# Pg4-Current_signal_condtioning.net
KiCad netlist of a schematic drawn in Altium Designer
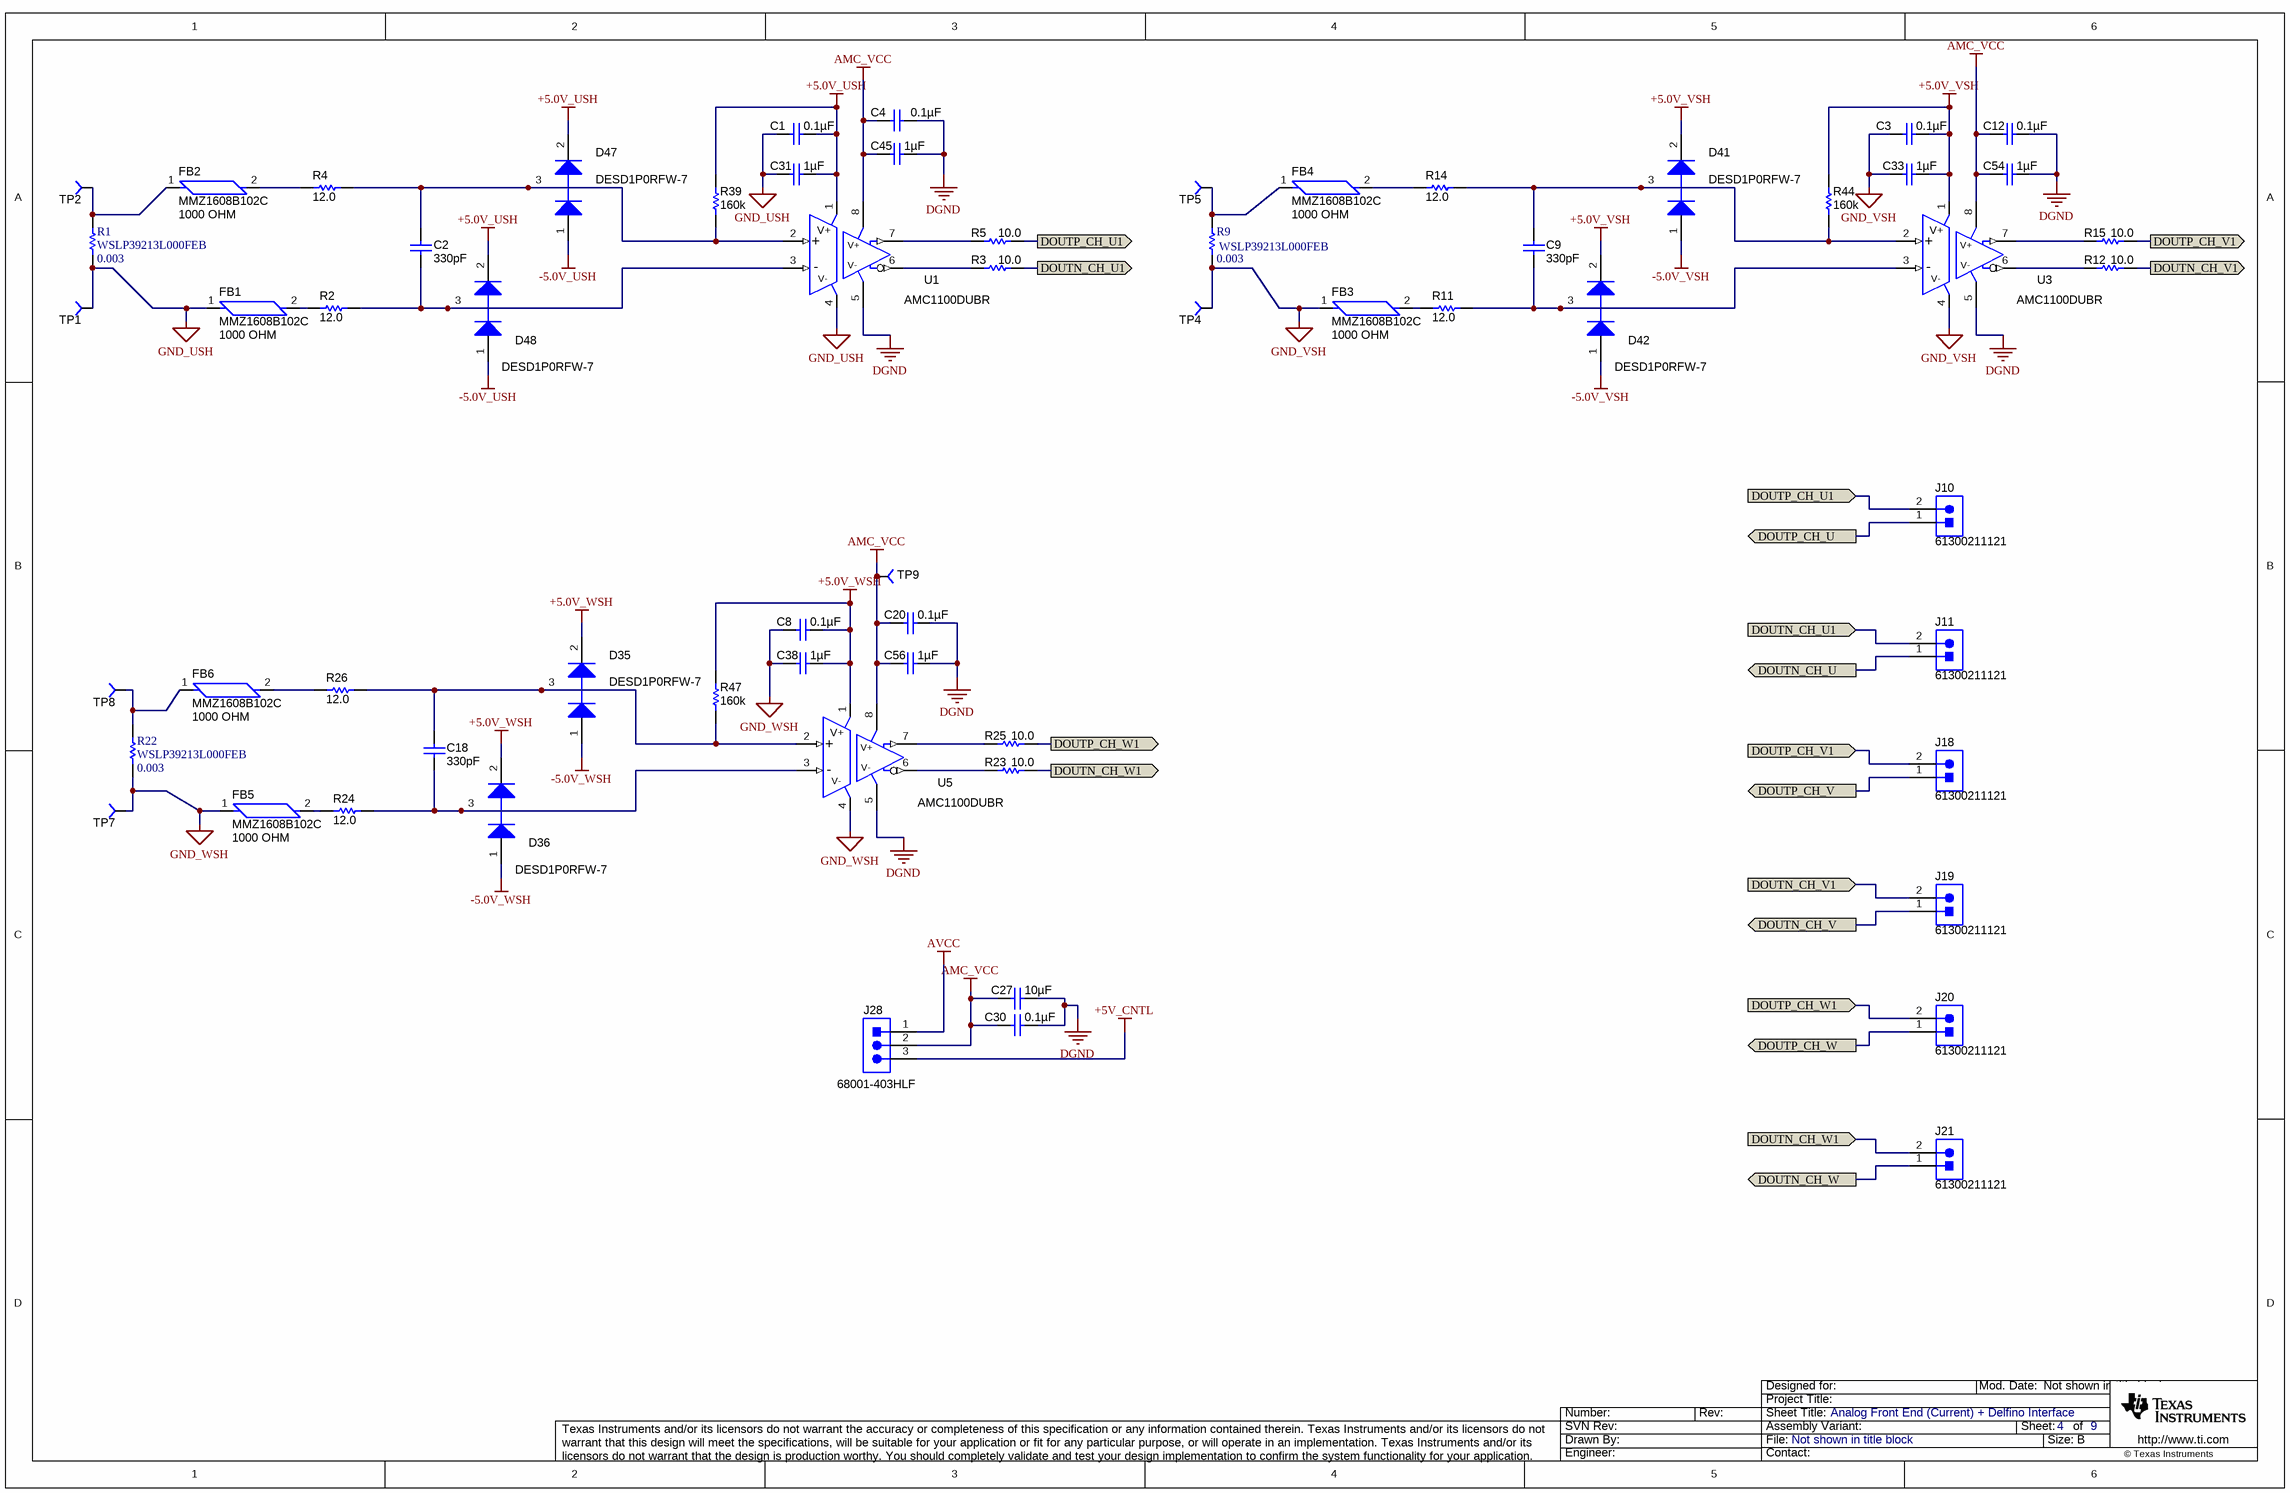
[diagram p0: Pg4-Current  signal condtioning.SchDoc]

(export (version "E")
  (design (tool "Eeschema 10.0.6"))
  (components
    (comp (ref "C1")
      (value "~")
      (footprint "0603")
      (description "CAP, CERM, 0.1uF, 25V, +/-5%, X7R, 0603")
      (fields
        (field (name "PARTNUMBER") "06033C104JAT2A")
        (field (name "VALUEDISPLAYED") "0.1µF")
        (field (name "MANUFACTURER") "AVX")
        (field (name "PUBLISHER") "Texas Instruments")
      )
      (libsource (lib "Capacitor_Ceramic") (part "06033C104JAT2A"))
    )
    (comp (ref "C2")
      (value "08055A331KAT2A")
      (footprint "0805_HV")
      (description "CAP, CERM, 330 pF, 50 V, +/- 10%, C0G/NP0, 0805")
      (fields
        (field (name "VALUEDISPLAYED") "330pF")
        (field (name "MANUFACTURER") "AVX")
        (field (name "PUBLISHER") "Texas Instruments")
      )
      (libsource (lib "Capacitor_Ceramic") (part "08055A331KAT2A"))
    )
    (comp (ref "C3")
      (value "~")
      (footprint "0603")
      (description "CAP, CERM, 0.1uF, 25V, +/-5%, X7R, 0603")
      (fields
        (field (name "PARTNUMBER") "06033C104JAT2A")
        (field (name "VALUEDISPLAYED") "0.1µF")
        (field (name "MANUFACTURER") "AVX")
        (field (name "PUBLISHER") "Texas Instruments")
      )
      (libsource (lib "Capacitor_Ceramic") (part "06033C104JAT2A"))
    )
    (comp (ref "C4")
      (value "~")
      (footprint "0603")
      (description "CAP, CERM, 0.1uF, 25V, +/-5%, X7R, 0603")
      (fields
        (field (name "PARTNUMBER") "06033C104JAT2A")
        (field (name "VALUEDISPLAYED") "0.1µF")
        (field (name "MANUFACTURER") "AVX")
        (field (name "PUBLISHER") "Texas Instruments")
      )
      (libsource (lib "Capacitor_Ceramic") (part "06033C104JAT2A"))
    )
    (comp (ref "C8")
      (value "~")
      (footprint "0603")
      (description "CAP, CERM, 0.1uF, 25V, +/-5%, X7R, 0603")
      (fields
        (field (name "PARTNUMBER") "06033C104JAT2A")
        (field (name "VALUEDISPLAYED") "0.1µF")
        (field (name "MANUFACTURER") "AVX")
        (field (name "PUBLISHER") "Texas Instruments")
      )
      (libsource (lib "Capacitor_Ceramic") (part "06033C104JAT2A"))
    )
    (comp (ref "C9")
      (value "08055A331KAT2A")
      (footprint "0805_HV")
      (description "CAP, CERM, 330 pF, 50 V, +/- 10%, C0G/NP0, 0805")
      (fields
        (field (name "VALUEDISPLAYED") "330pF")
        (field (name "MANUFACTURER") "AVX")
        (field (name "PUBLISHER") "Texas Instruments")
      )
      (libsource (lib "Capacitor_Ceramic") (part "08055A331KAT2A"))
    )
    (comp (ref "C12")
      (value "~")
      (footprint "0603")
      (description "CAP, CERM, 0.1uF, 25V, +/-5%, X7R, 0603")
      (fields
        (field (name "PARTNUMBER") "06033C104JAT2A")
        (field (name "VALUEDISPLAYED") "0.1µF")
        (field (name "MANUFACTURER") "AVX")
        (field (name "PUBLISHER") "Texas Instruments")
      )
      (libsource (lib "Capacitor_Ceramic") (part "06033C104JAT2A"))
    )
    (comp (ref "C18")
      (value "08055A331KAT2A")
      (footprint "0805_HV")
      (description "CAP, CERM, 330 pF, 50 V, +/- 10%, C0G/NP0, 0805")
      (fields
        (field (name "VALUEDISPLAYED") "330pF")
        (field (name "MANUFACTURER") "AVX")
        (field (name "PUBLISHER") "Texas Instruments")
      )
      (libsource (lib "Capacitor_Ceramic") (part "08055A331KAT2A"))
    )
    (comp (ref "C20")
      (value "~")
      (footprint "0603")
      (description "CAP, CERM, 0.1uF, 25V, +/-5%, X7R, 0603")
      (fields
        (field (name "PARTNUMBER") "06033C104JAT2A")
        (field (name "VALUEDISPLAYED") "0.1µF")
        (field (name "MANUFACTURER") "AVX")
        (field (name "PUBLISHER") "Texas Instruments")
      )
      (libsource (lib "Capacitor_Ceramic") (part "06033C104JAT2A"))
    )
    (comp (ref "C27")
      (value "~")
      (footprint "1210")
      (description "CAP, CERM, 10uF, 35V, +/-20%, X7R, 1210")
      (fields
        (field (name "PARTNUMBER") "GMK325AB7106MM-T")
        (field (name "VALUEDISPLAYED") "10µF")
        (field (name "MANUFACTURER") "Taiyo Yuden")
        (field (name "PUBLISHER") "Texas Instruments")
      )
      (libsource (lib "Capacitor_Ceramic") (part "GMK325AB7106MM-T"))
    )
    (comp (ref "C30")
      (value "~")
      (footprint "0603")
      (description "CAP, CERM, 0.1uF, 50V, +/-10%, X7R, 0603")
      (fields
        (field (name "PARTNUMBER") "C0603C104K5RACTU")
        (field (name "VALUEDISPLAYED") "0.1µF")
        (field (name "MANUFACTURER") "Kemet")
        (field (name "PUBLISHER") "Texas Instruments")
      )
      (libsource (lib "Capacitor_Ceramic") (part "C0603C104K5RACTU"))
    )
    (comp (ref "C31")
      (value "GRM188R71C105KA12D")
      (footprint "0603")
      (description "CAP, CERM, 1 µF, 16 V, +/- 10%, X7R, 0603")
      (fields
        (field (name "VALUEDISPLAYED") "1µF")
        (field (name "MANUFACTURER") "MuRata")
        (field (name "PUBLISHER") "Texas Instruments")
      )
      (libsource (lib "Capacitor_Ceramic") (part "GRM188R71C105KA12D"))
    )
    (comp (ref "C33")
      (value "GRM188R71C105KA12D")
      (footprint "0603")
      (description "CAP, CERM, 1 µF, 16 V, +/- 10%, X7R, 0603")
      (fields
        (field (name "VALUEDISPLAYED") "1µF")
        (field (name "MANUFACTURER") "MuRata")
        (field (name "PUBLISHER") "Texas Instruments")
      )
      (libsource (lib "Capacitor_Ceramic") (part "GRM188R71C105KA12D"))
    )
    (comp (ref "C38")
      (value "GRM188R71C105KA12D")
      (footprint "0603")
      (description "CAP, CERM, 1 µF, 16 V, +/- 10%, X7R, 0603")
      (fields
        (field (name "VALUEDISPLAYED") "1µF")
        (field (name "MANUFACTURER") "MuRata")
        (field (name "PUBLISHER") "Texas Instruments")
      )
      (libsource (lib "Capacitor_Ceramic") (part "GRM188R71C105KA12D"))
    )
    (comp (ref "C45")
      (value "GRM188R71C105KA12D")
      (footprint "0603")
      (description "CAP, CERM, 1 µF, 16 V, +/- 10%, X7R, 0603")
      (fields
        (field (name "VALUEDISPLAYED") "1µF")
        (field (name "MANUFACTURER") "MuRata")
        (field (name "PUBLISHER") "Texas Instruments")
      )
      (libsource (lib "Capacitor_Ceramic") (part "GRM188R71C105KA12D"))
    )
    (comp (ref "C54")
      (value "GRM188R71C105KA12D")
      (footprint "0603")
      (description "CAP, CERM, 1 µF, 16 V, +/- 10%, X7R, 0603")
      (fields
        (field (name "VALUEDISPLAYED") "1µF")
        (field (name "MANUFACTURER") "MuRata")
        (field (name "PUBLISHER") "Texas Instruments")
      )
      (libsource (lib "Capacitor_Ceramic") (part "GRM188R71C105KA12D"))
    )
    (comp (ref "C56")
      (value "GRM188R71C105KA12D")
      (footprint "0603")
      (description "CAP, CERM, 1 µF, 16 V, +/- 10%, X7R, 0603")
      (fields
        (field (name "VALUEDISPLAYED") "1µF")
        (field (name "MANUFACTURER") "MuRata")
        (field (name "PUBLISHER") "Texas Instruments")
      )
      (libsource (lib "Capacitor_Ceramic") (part "GRM188R71C105KA12D"))
    )
    (comp (ref "D35")
      (value "DESD1P0RFW-7")
      (footprint "SOT-323")
      (description "Diode, P-N, 70V, 0.2A, SOT-323")
      (fields (field (name "MANUFACTURER") "Diodes Inc") (field (name "PUBLISHER") "Texas Instruments"))
      (libsource (lib "Diode") (part "BAV99WT1G"))
    )
    (comp (ref "D36")
      (value "DESD1P0RFW-7")
      (footprint "SOT-323")
      (description "Diode, P-N, 70V, 0.2A, SOT-323")
      (fields (field (name "MANUFACTURER") "Diodes Inc") (field (name "PUBLISHER") "Texas Instruments"))
      (libsource (lib "Diode") (part "BAV99WT1G"))
    )
    (comp (ref "D41")
      (value "DESD1P0RFW-7")
      (footprint "SOT-323")
      (description "Diode, P-N, 70V, 0.2A, SOT-323")
      (fields (field (name "MANUFACTURER") "Diodes Inc") (field (name "PUBLISHER") "Texas Instruments"))
      (libsource (lib "Diode") (part "BAV99WT1G"))
    )
    (comp (ref "D42")
      (value "DESD1P0RFW-7")
      (footprint "SOT-323")
      (description "Diode, P-N, 70V, 0.2A, SOT-323")
      (fields (field (name "MANUFACTURER") "Diodes Inc") (field (name "PUBLISHER") "Texas Instruments"))
      (libsource (lib "Diode") (part "BAV99WT1G"))
    )
    (comp (ref "D47")
      (value "DESD1P0RFW-7")
      (footprint "SOT-323")
      (description "Diode, P-N, 70V, 0.2A, SOT-323")
      (fields (field (name "MANUFACTURER") "Diodes Inc") (field (name "PUBLISHER") "Texas Instruments"))
      (libsource (lib "Diode") (part "BAV99WT1G"))
    )
    (comp (ref "D48")
      (value "DESD1P0RFW-7")
      (footprint "SOT-323")
      (description "Diode, P-N, 70V, 0.2A, SOT-323")
      (fields (field (name "MANUFACTURER") "Diodes Inc") (field (name "PUBLISHER") "Texas Instruments"))
      (libsource (lib "Diode") (part "BAV99WT1G"))
    )
    (comp (ref "FB1")
      (value "MMZ1608B102C")
      (footprint "FB0603")
      (description "FERRITE CHIP 1000 OHM 300MA 0603")
      (fields
        (field (name "MANUFACTURER") "TDK Corporation")
        (field (name "ALTIUM_VALUE") "1000 OHM")
        (field (name "PUBLISHER") "TI")
      )
      (libsource (lib "Isolated current sensing") (part "MMZ1608B102C"))
    )
    (comp (ref "FB2")
      (value "MMZ1608B102C")
      (footprint "FB0603")
      (description "FERRITE CHIP 1000 OHM 300MA 0603")
      (fields
        (field (name "MANUFACTURER") "TDK Corporation")
        (field (name "ALTIUM_VALUE") "1000 OHM")
        (field (name "PUBLISHER") "TI")
      )
      (libsource (lib "Isolated current sensing") (part "MMZ1608B102C"))
    )
    (comp (ref "FB3")
      (value "MMZ1608B102C")
      (footprint "FB0603")
      (description "FERRITE CHIP 1000 OHM 300MA 0603")
      (fields
        (field (name "MANUFACTURER") "TDK Corporation")
        (field (name "ALTIUM_VALUE") "1000 OHM")
        (field (name "PUBLISHER") "TI")
      )
      (libsource (lib "Isolated current sensing") (part "MMZ1608B102C"))
    )
    (comp (ref "FB4")
      (value "MMZ1608B102C")
      (footprint "FB0603")
      (description "FERRITE CHIP 1000 OHM 300MA 0603")
      (fields
        (field (name "MANUFACTURER") "TDK Corporation")
        (field (name "ALTIUM_VALUE") "1000 OHM")
        (field (name "PUBLISHER") "TI")
      )
      (libsource (lib "Isolated current sensing") (part "MMZ1608B102C"))
    )
    (comp (ref "FB5")
      (value "MMZ1608B102C")
      (footprint "FB0603")
      (description "FERRITE CHIP 1000 OHM 300MA 0603")
      (fields
        (field (name "MANUFACTURER") "TDK Corporation")
        (field (name "ALTIUM_VALUE") "1000 OHM")
        (field (name "PUBLISHER") "TI")
      )
      (libsource (lib "Isolated current sensing") (part "MMZ1608B102C"))
    )
    (comp (ref "FB6")
      (value "MMZ1608B102C")
      (footprint "FB0603")
      (description "FERRITE CHIP 1000 OHM 300MA 0603")
      (fields
        (field (name "MANUFACTURER") "TDK Corporation")
        (field (name "ALTIUM_VALUE") "1000 OHM")
        (field (name "PUBLISHER") "TI")
      )
      (libsource (lib "Isolated current sensing") (part "MMZ1608B102C"))
    )
    (comp (ref "J10")
      (value "61300211121")
      (footprint "WURTH_61300211121")
      (description "Header, 2.54 mm, 2x1, Gold, TH")
      (fields
        (field (name "MANUFACTURER") "Wurth Elektronik eiSos")
        (field (name "SYMBOLCREATOR") "a0412235")
        (field (name "PUBLISHER") "Texas Instruments")
      )
      (libsource (lib "Connectors") (part "61300211121"))
    )
    (comp (ref "J11")
      (value "61300211121")
      (footprint "WURTH_61300211121")
      (description "Header, 2.54 mm, 2x1, Gold, TH")
      (fields
        (field (name "MANUFACTURER") "Wurth Elektronik eiSos")
        (field (name "SYMBOLCREATOR") "a0412235")
        (field (name "PUBLISHER") "Texas Instruments")
      )
      (libsource (lib "Connectors") (part "61300211121"))
    )
    (comp (ref "J18")
      (value "61300211121")
      (footprint "WURTH_61300211121")
      (description "Header, 2.54 mm, 2x1, Gold, TH")
      (fields
        (field (name "MANUFACTURER") "Wurth Elektronik eiSos")
        (field (name "SYMBOLCREATOR") "a0412235")
        (field (name "PUBLISHER") "Texas Instruments")
      )
      (libsource (lib "Connectors") (part "61300211121"))
    )
    (comp (ref "J19")
      (value "61300211121")
      (footprint "WURTH_61300211121")
      (description "Header, 2.54 mm, 2x1, Gold, TH")
      (fields
        (field (name "MANUFACTURER") "Wurth Elektronik eiSos")
        (field (name "SYMBOLCREATOR") "a0412235")
        (field (name "PUBLISHER") "Texas Instruments")
      )
      (libsource (lib "Connectors") (part "61300211121"))
    )
    (comp (ref "J20")
      (value "61300211121")
      (footprint "WURTH_61300211121")
      (description "Header, 2.54 mm, 2x1, Gold, TH")
      (fields
        (field (name "MANUFACTURER") "Wurth Elektronik eiSos")
        (field (name "SYMBOLCREATOR") "a0412235")
        (field (name "PUBLISHER") "Texas Instruments")
      )
      (libsource (lib "Connectors") (part "61300211121"))
    )
    (comp (ref "J21")
      (value "61300211121")
      (footprint "WURTH_61300211121")
      (description "Header, 2.54 mm, 2x1, Gold, TH")
      (fields
        (field (name "MANUFACTURER") "Wurth Elektronik eiSos")
        (field (name "SYMBOLCREATOR") "a0412235")
        (field (name "PUBLISHER") "Texas Instruments")
      )
      (libsource (lib "Connectors") (part "61300211121"))
    )
    (comp (ref "J28")
      (value "68001-403HLF")
      (footprint "HDR1X3")
      (description "3 pin berger")
      (fields
        (field (name "MANUFACTURER") "FCI")
        (field (name "SYMBOLCREATOR") "a0799628")
        (field (name "PUBLISHER") "Texas Instruments")
      )
      (libsource (lib "Connectors") (part "009155003301006"))
    )
    (comp (ref "R1")
      (value "WSLP39213L000FEB")
      (footprint "RC3921")
      (description "RESISTOR, SMD, 0.003 OHM, 1%, 5W, 3921")
      (fields
        (field (name "MANUFACTURER") "VISHAY DALE")
        (field (name "ALTIUM_VALUE") "0.003")
        (field (name "SYMBOLCREATOR") "x0199378")
      )
      (libsource (lib "TS11406AC0_TIDA-00555") (part "WSLP39213L000FEB"))
    )
    (comp (ref "R2")
      (value "RC0603FR-0712RL")
      (footprint "0603")
      (description "RES, 12.0, 1%, 0.1 W, 0603")
      (fields
        (field (name "VALUEDISPLAYED") "12.0")
        (field (name "MANUFACTURER") "Yageo America")
        (field (name "PUBLISHER") "Texas Instruments")
      )
      (libsource (lib "Resistor_0603") (part "RC0603FR-0712RL"))
    )
    (comp (ref "R3")
      (value "10.0")
      (footprint "0603")
      (description "RES, 10.0 ohm, 1%, 0.1W, 0603")
      (fields
        (field (name "PARTNUMBER") "CRCW060310R0FKEA")
        (field (name "MANUFACTURER") "Vishay-Dale")
        (field (name "PUBLISHER") "Texas Instruments")
      )
      (libsource (lib "Resistor_0603") (part "CRCW060310R0FKEA"))
    )
    (comp (ref "R4")
      (value "RC0603FR-0712RL")
      (footprint "0603")
      (description "RES, 12.0, 1%, 0.1 W, 0603")
      (fields
        (field (name "VALUEDISPLAYED") "12.0")
        (field (name "MANUFACTURER") "Yageo America")
        (field (name "PUBLISHER") "Texas Instruments")
      )
      (libsource (lib "Resistor_0603") (part "RC0603FR-0712RL"))
    )
    (comp (ref "R5")
      (value "10.0")
      (footprint "0603")
      (description "RES, 10.0 ohm, 1%, 0.1W, 0603")
      (fields
        (field (name "PARTNUMBER") "CRCW060310R0FKEA")
        (field (name "MANUFACTURER") "Vishay-Dale")
        (field (name "PUBLISHER") "Texas Instruments")
      )
      (libsource (lib "Resistor_0603") (part "CRCW060310R0FKEA"))
    )
    (comp (ref "R9")
      (value "WSLP39213L000FEB")
      (footprint "RC3921")
      (description "RESISTOR, SMD, 0.003 OHM, 1%, 5W, 3921")
      (fields
        (field (name "MANUFACTURER") "VISHAY DALE")
        (field (name "ALTIUM_VALUE") "0.003")
        (field (name "SYMBOLCREATOR") "x0199378")
      )
      (libsource (lib "TS11406AC0_TIDA-00555") (part "WSLP39213L000FEB"))
    )
    (comp (ref "R11")
      (value "RC0603FR-0712RL")
      (footprint "0603")
      (description "RES, 12.0, 1%, 0.1 W, 0603")
      (fields
        (field (name "VALUEDISPLAYED") "12.0")
        (field (name "MANUFACTURER") "Yageo America")
        (field (name "PUBLISHER") "Texas Instruments")
      )
      (libsource (lib "Resistor_0603") (part "RC0603FR-0712RL"))
    )
    (comp (ref "R12")
      (value "10.0")
      (footprint "0603")
      (description "RES, 10.0 ohm, 1%, 0.1W, 0603")
      (fields
        (field (name "PARTNUMBER") "CRCW060310R0FKEA")
        (field (name "MANUFACTURER") "Vishay-Dale")
        (field (name "PUBLISHER") "Texas Instruments")
      )
      (libsource (lib "Resistor_0603") (part "CRCW060310R0FKEA"))
    )
    (comp (ref "R14")
      (value "RC0603FR-0712RL")
      (footprint "0603")
      (description "RES, 12.0, 1%, 0.1 W, 0603")
      (fields
        (field (name "VALUEDISPLAYED") "12.0")
        (field (name "MANUFACTURER") "Yageo America")
        (field (name "PUBLISHER") "Texas Instruments")
      )
      (libsource (lib "Resistor_0603") (part "RC0603FR-0712RL"))
    )
    (comp (ref "R15")
      (value "10.0")
      (footprint "0603")
      (description "RES, 10.0 ohm, 1%, 0.1W, 0603")
      (fields
        (field (name "PARTNUMBER") "CRCW060310R0FKEA")
        (field (name "MANUFACTURER") "Vishay-Dale")
        (field (name "PUBLISHER") "Texas Instruments")
      )
      (libsource (lib "Resistor_0603") (part "CRCW060310R0FKEA"))
    )
    (comp (ref "R22")
      (value "WSLP39213L000FEB")
      (footprint "RC3921")
      (description "RESISTOR, SMD, 0.003 OHM, 1%, 5W, 3921")
      (fields
        (field (name "MANUFACTURER") "VISHAY DALE")
        (field (name "ALTIUM_VALUE") "0.003")
        (field (name "SYMBOLCREATOR") "x0199378")
      )
      (libsource (lib "TS11406AC0_TIDA-00555") (part "WSLP39213L000FEB"))
    )
    (comp (ref "R23")
      (value "10.0")
      (footprint "0603")
      (description "RES, 10.0 ohm, 1%, 0.1W, 0603")
      (fields
        (field (name "PARTNUMBER") "CRCW060310R0FKEA")
        (field (name "MANUFACTURER") "Vishay-Dale")
        (field (name "PUBLISHER") "Texas Instruments")
      )
      (libsource (lib "Resistor_0603") (part "CRCW060310R0FKEA"))
    )
    (comp (ref "R24")
      (value "RC0603FR-0712RL")
      (footprint "0603")
      (description "RES, 12.0, 1%, 0.1 W, 0603")
      (fields
        (field (name "VALUEDISPLAYED") "12.0")
        (field (name "MANUFACTURER") "Yageo America")
        (field (name "PUBLISHER") "Texas Instruments")
      )
      (libsource (lib "Resistor_0603") (part "RC0603FR-0712RL"))
    )
    (comp (ref "R25")
      (value "10.0")
      (footprint "0603")
      (description "RES, 10.0 ohm, 1%, 0.1W, 0603")
      (fields
        (field (name "PARTNUMBER") "CRCW060310R0FKEA")
        (field (name "MANUFACTURER") "Vishay-Dale")
        (field (name "PUBLISHER") "Texas Instruments")
      )
      (libsource (lib "Resistor_0603") (part "CRCW060310R0FKEA"))
    )
    (comp (ref "R26")
      (value "RC0603FR-0712RL")
      (footprint "0603")
      (description "RES, 12.0, 1%, 0.1 W, 0603")
      (fields
        (field (name "VALUEDISPLAYED") "12.0")
        (field (name "MANUFACTURER") "Yageo America")
        (field (name "PUBLISHER") "Texas Instruments")
      )
      (libsource (lib "Resistor_0603") (part "RC0603FR-0712RL"))
    )
    (comp (ref "R39")
      (value "CRCW0603160KFKEA")
      (footprint "0603")
      (description "RES, 160 k, 1%, 0.1 W, 0603")
      (fields
        (field (name "MANUFACTURER") "Vishay-Dale")
        (field (name "VALUEDISPLAYED") "160k")
        (field (name "PUBLISHER") "Texas Instruments")
      )
      (libsource (lib "Resistor_0603") (part "CRCW0603160KFKEA"))
    )
    (comp (ref "R44")
      (value "CRCW0603160KFKEA")
      (footprint "0603")
      (description "RES, 160 k, 1%, 0.1 W, 0603")
      (fields
        (field (name "MANUFACTURER") "Vishay-Dale")
        (field (name "VALUEDISPLAYED") "160k")
        (field (name "PUBLISHER") "Texas Instruments")
      )
      (libsource (lib "Resistor_0603") (part "CRCW0603160KFKEA"))
    )
    (comp (ref "R47")
      (value "CRCW0603160KFKEA")
      (footprint "0603")
      (description "RES, 160 k, 1%, 0.1 W, 0603")
      (fields
        (field (name "MANUFACTURER") "Vishay-Dale")
        (field (name "VALUEDISPLAYED") "160k")
        (field (name "PUBLISHER") "Texas Instruments")
      )
      (libsource (lib "Resistor_0603") (part "CRCW0603160KFKEA"))
    )
    (comp (ref "TP1")
      (value "TP-5001-BLACK")
      (footprint "TH-40")
      (description "Test Point,  Black, Thru Hole Color Keyed")
      (fields (field (name "MANUFACTURER") "Keystone") (field (name "PARTNUMBER") "5001"))
      (libsource (lib "PADSlegacy_Hardware") (part "TP-5001-BLACK"))
    )
    (comp (ref "TP2")
      (value "TP-5001-BLACK")
      (footprint "TH-40")
      (description "Test Point,  Black, Thru Hole Color Keyed")
      (fields (field (name "MANUFACTURER") "Keystone") (field (name "PARTNUMBER") "5001"))
      (libsource (lib "PADSlegacy_Hardware") (part "TP-5001-BLACK"))
    )
    (comp (ref "TP4")
      (value "TP-5001-BLACK")
      (footprint "TH-40")
      (description "Test Point,  Black, Thru Hole Color Keyed")
      (fields (field (name "MANUFACTURER") "Keystone") (field (name "PARTNUMBER") "5001"))
      (libsource (lib "PADSlegacy_Hardware") (part "TP-5001-BLACK"))
    )
    (comp (ref "TP5")
      (value "TP-5001-BLACK")
      (footprint "TH-40")
      (description "Test Point,  Black, Thru Hole Color Keyed")
      (fields (field (name "MANUFACTURER") "Keystone") (field (name "PARTNUMBER") "5001"))
      (libsource (lib "PADSlegacy_Hardware") (part "TP-5001-BLACK"))
    )
    (comp (ref "TP7")
      (value "TP-5001-BLACK")
      (footprint "TH-40")
      (description "Test Point,  Black, Thru Hole Color Keyed")
      (fields (field (name "MANUFACTURER") "Keystone") (field (name "PARTNUMBER") "5001"))
      (libsource (lib "PADSlegacy_Hardware") (part "TP-5001-BLACK"))
    )
    (comp (ref "TP8")
      (value "TP-5001-BLACK")
      (footprint "TH-40")
      (description "Test Point,  Black, Thru Hole Color Keyed")
      (fields (field (name "MANUFACTURER") "Keystone") (field (name "PARTNUMBER") "5001"))
      (libsource (lib "PADSlegacy_Hardware") (part "TP-5001-BLACK"))
    )
    (comp (ref "TP9")
      (value "~")
      (footprint "TP-040_RND")
      (description "Test Point, O.040 Hole")
      (fields (field (name "MANUFACTURER") "STD"))
      (libsource (lib "PADSlegacy_Hardware") (part "TP-040_RND"))
    )
    (comp (ref "U1")
      (value "AMC1100DUBR")
      (footprint "DUB0008A_N")
      (description "Fully-Differential Isolation Amplifier, DUB0008A")
      (fields
        (field (name "ALTERNATE PARTNUMBER") "AMC1100DUB")
        (field (name "MANUFACTURER") "Texas Instruments")
        (field (name "SYMBOLCREATOR") "a0411947")
        (field (name "PUBLISHER") "Texas Instruments")
      )
      (libsource (lib "TI_Pre_RTM") (part "AMC1100DUBR"))
    )
    (comp (ref "U3")
      (value "AMC1100DUBR")
      (footprint "DUB0008A_N")
      (description "Fully-Differential Isolation Amplifier, DUB0008A")
      (fields
        (field (name "ALTERNATE PARTNUMBER") "AMC1100DUB")
        (field (name "MANUFACTURER") "Texas Instruments")
        (field (name "SYMBOLCREATOR") "a0411947")
        (field (name "PUBLISHER") "Texas Instruments")
      )
      (libsource (lib "TI_Pre_RTM") (part "AMC1100DUBR"))
    )
    (comp (ref "U5")
      (value "AMC1100DUBR")
      (footprint "DUB0008A_N")
      (description "Fully-Differential Isolation Amplifier, DUB0008A")
      (fields
        (field (name "ALTERNATE PARTNUMBER") "AMC1100DUB")
        (field (name "MANUFACTURER") "Texas Instruments")
        (field (name "SYMBOLCREATOR") "a0411947")
        (field (name "PUBLISHER") "Texas Instruments")
      )
      (libsource (lib "TI_Pre_RTM") (part "AMC1100DUBR"))
    )
  )
  (nets
    (net (code "1") (name "+5.0V_USH") (class "Default")
      (node (ref "C1") (pin "1") (pinfunction "1_1") (pintype "passive"))
      (node (ref "C31") (pin "2") (pinfunction "2_2") (pintype "passive"))
      (node (ref "D47") (pin "2") (pinfunction "K_2") (pintype "passive"))
      (node (ref "D48") (pin "2") (pinfunction "K_2") (pintype "passive"))
      (node (ref "R39") (pin "2") (pinfunction "2_2") (pintype "passive"))
      (node (ref "U1") (pin "1") (pinfunction "VDD1_1") (pintype "power_in"))
    )
    (net (code "2") (name "+5.0V_VSH") (class "Default")
      (node (ref "C3") (pin "1") (pinfunction "1_1") (pintype "passive"))
      (node (ref "C33") (pin "2") (pinfunction "2_2") (pintype "passive"))
      (node (ref "D41") (pin "2") (pinfunction "K_2") (pintype "passive"))
      (node (ref "D42") (pin "2") (pinfunction "K_2") (pintype "passive"))
      (node (ref "R44") (pin "2") (pinfunction "2_2") (pintype "passive"))
      (node (ref "U3") (pin "1") (pinfunction "VDD1_1") (pintype "power_in"))
    )
    (net (code "3") (name "+5.0V_WSH") (class "Default")
      (node (ref "C38") (pin "2") (pinfunction "2_2") (pintype "passive"))
      (node (ref "C8") (pin "1") (pinfunction "1_1") (pintype "passive"))
      (node (ref "D35") (pin "2") (pinfunction "K_2") (pintype "passive"))
      (node (ref "D36") (pin "2") (pinfunction "K_2") (pintype "passive"))
      (node (ref "R47") (pin "2") (pinfunction "2_2") (pintype "passive"))
      (node (ref "U5") (pin "1") (pinfunction "VDD1_1") (pintype "power_in"))
    )
    (net (code "4") (name "+5V_CNTL") (class "Default")
      (node (ref "J28") (pin "3") (pinfunction "3_3") (pintype "passive"))
    )
    (net (code "5") (name "-5.0V_USH") (class "Default")
      (node (ref "D47") (pin "1") (pinfunction "A_1") (pintype "passive"))
      (node (ref "D48") (pin "1") (pinfunction "A_1") (pintype "passive"))
    )
    (net (code "6") (name "-5.0V_VSH") (class "Default")
      (node (ref "D41") (pin "1") (pinfunction "A_1") (pintype "passive"))
      (node (ref "D42") (pin "1") (pinfunction "A_1") (pintype "passive"))
    )
    (net (code "7") (name "-5.0V_WSH") (class "Default")
      (node (ref "D35") (pin "1") (pinfunction "A_1") (pintype "passive"))
      (node (ref "D36") (pin "1") (pinfunction "A_1") (pintype "passive"))
    )
    (net (code "8") (name "/DOUTN_CH_U") (class "Default")
      (node (ref "J11") (pin "1") (pinfunction "1_1") (pintype "passive"))
    )
    (net (code "9") (name "/DOUTN_CH_U1") (class "Default")
      (node (ref "J11") (pin "2") (pinfunction "2_2") (pintype "passive"))
      (node (ref "R3") (pin "2") (pinfunction "2_2") (pintype "passive"))
    )
    (net (code "10") (name "/DOUTN_CH_V") (class "Default")
      (node (ref "J19") (pin "1") (pinfunction "1_1") (pintype "passive"))
    )
    (net (code "11") (name "/DOUTN_CH_V1") (class "Default")
      (node (ref "J19") (pin "2") (pinfunction "2_2") (pintype "passive"))
      (node (ref "R12") (pin "2") (pinfunction "2_2") (pintype "passive"))
    )
    (net (code "12") (name "/DOUTN_CH_W") (class "Default")
      (node (ref "J21") (pin "1") (pinfunction "1_1") (pintype "passive"))
    )
    (net (code "13") (name "/DOUTN_CH_W1") (class "Default")
      (node (ref "J21") (pin "2") (pinfunction "2_2") (pintype "passive"))
      (node (ref "R23") (pin "2") (pinfunction "2_2") (pintype "passive"))
    )
    (net (code "14") (name "/DOUTP_CH_U") (class "Default")
      (node (ref "J10") (pin "1") (pinfunction "1_1") (pintype "passive"))
    )
    (net (code "15") (name "/DOUTP_CH_U1") (class "Default")
      (node (ref "J10") (pin "2") (pinfunction "2_2") (pintype "passive"))
      (node (ref "R5") (pin "2") (pinfunction "2_2") (pintype "passive"))
    )
    (net (code "16") (name "/DOUTP_CH_V") (class "Default")
      (node (ref "J18") (pin "1") (pinfunction "1_1") (pintype "passive"))
    )
    (net (code "17") (name "/DOUTP_CH_V1") (class "Default")
      (node (ref "J18") (pin "2") (pinfunction "2_2") (pintype "passive"))
      (node (ref "R15") (pin "2") (pinfunction "2_2") (pintype "passive"))
    )
    (net (code "18") (name "/DOUTP_CH_W") (class "Default")
      (node (ref "J20") (pin "1") (pinfunction "1_1") (pintype "passive"))
    )
    (net (code "19") (name "/DOUTP_CH_W1") (class "Default")
      (node (ref "J20") (pin "2") (pinfunction "2_2") (pintype "passive"))
      (node (ref "R25") (pin "2") (pinfunction "2_2") (pintype "passive"))
    )
    (net (code "20") (name "AMC_VCC") (class "Default")
      (node (ref "C12") (pin "2") (pinfunction "2_2") (pintype "passive"))
      (node (ref "C20") (pin "2") (pinfunction "2_2") (pintype "passive"))
      (node (ref "C27") (pin "1") (pinfunction "1_1") (pintype "passive"))
      (node (ref "C30") (pin "1") (pinfunction "1_1") (pintype "passive"))
      (node (ref "C4") (pin "2") (pinfunction "2_2") (pintype "passive"))
      (node (ref "C45") (pin "1") (pinfunction "1_1") (pintype "passive"))
      (node (ref "C54") (pin "1") (pinfunction "1_1") (pintype "passive"))
      (node (ref "C56") (pin "1") (pinfunction "1_1") (pintype "passive"))
      (node (ref "J28") (pin "2") (pinfunction "2_2") (pintype "passive"))
      (node (ref "TP9") (pin "1") (pinfunction "1_1") (pintype "passive"))
      (node (ref "U1") (pin "8") (pinfunction "VDD2_8") (pintype "power_in"))
      (node (ref "U3") (pin "8") (pinfunction "VDD2_8") (pintype "power_in"))
      (node (ref "U5") (pin "8") (pinfunction "VDD2_8") (pintype "power_in"))
    )
    (net (code "21") (name "AVCC") (class "Default")
      (node (ref "J28") (pin "1") (pinfunction "1_1") (pintype "passive"))
    )
    (net (code "22") (name "DGND") (class "Default")
      (node (ref "C12") (pin "1") (pinfunction "1_1") (pintype "passive"))
      (node (ref "C20") (pin "1") (pinfunction "1_1") (pintype "passive"))
      (node (ref "C27") (pin "2") (pinfunction "2_2") (pintype "passive"))
      (node (ref "C30") (pin "2") (pinfunction "2_2") (pintype "passive"))
      (node (ref "C4") (pin "1") (pinfunction "1_1") (pintype "passive"))
      (node (ref "C45") (pin "2") (pinfunction "2_2") (pintype "passive"))
      (node (ref "C54") (pin "2") (pinfunction "2_2") (pintype "passive"))
      (node (ref "C56") (pin "2") (pinfunction "2_2") (pintype "passive"))
      (node (ref "U1") (pin "5") (pinfunction "GND2_5") (pintype "power_in"))
      (node (ref "U3") (pin "5") (pinfunction "GND2_5") (pintype "power_in"))
      (node (ref "U5") (pin "5") (pinfunction "GND2_5") (pintype "power_in"))
    )
    (net (code "23") (name "GND_USH") (class "Default")
      (node (ref "C1") (pin "2") (pinfunction "2_2") (pintype "passive"))
      (node (ref "C31") (pin "1") (pinfunction "1_1") (pintype "passive"))
      (node (ref "FB1") (pin "1") (pinfunction "1_1") (pintype "passive"))
      (node (ref "R1") (pin "1") (pinfunction "1_1") (pintype "passive"))
      (node (ref "TP1") (pin "1") (pinfunction "1_1") (pintype "passive"))
      (node (ref "U1") (pin "4") (pinfunction "GND1_4") (pintype "power_in"))
    )
    (net (code "24") (name "GND_VSH") (class "Default")
      (node (ref "C3") (pin "2") (pinfunction "2_2") (pintype "passive"))
      (node (ref "C33") (pin "1") (pinfunction "1_1") (pintype "passive"))
      (node (ref "FB3") (pin "1") (pinfunction "1_1") (pintype "passive"))
      (node (ref "R9") (pin "1") (pinfunction "1_1") (pintype "passive"))
      (node (ref "TP4") (pin "1") (pinfunction "1_1") (pintype "passive"))
      (node (ref "U3") (pin "4") (pinfunction "GND1_4") (pintype "power_in"))
    )
    (net (code "25") (name "GND_WSH") (class "Default")
      (node (ref "C38") (pin "1") (pinfunction "1_1") (pintype "passive"))
      (node (ref "C8") (pin "2") (pinfunction "2_2") (pintype "passive"))
      (node (ref "FB5") (pin "1") (pinfunction "1_1") (pintype "passive"))
      (node (ref "R22") (pin "1") (pinfunction "1_1") (pintype "passive"))
      (node (ref "TP7") (pin "1") (pinfunction "1_1") (pintype "passive"))
      (node (ref "U5") (pin "4") (pinfunction "GND1_4") (pintype "power_in"))
    )
    (net (code "26") (name "Net-(D35-C)") (class "Default")
      (node (ref "C18") (pin "1") (pinfunction "1_1") (pintype "passive"))
      (node (ref "D35") (pin "3") (pinfunction "C_3") (pintype "passive"))
      (node (ref "R26") (pin "2") (pinfunction "2_2") (pintype "passive"))
      (node (ref "R47") (pin "1") (pinfunction "1_1") (pintype "passive"))
      (node (ref "U5") (pin "2") (pinfunction "VINP_2") (pintype "input"))
    )
    (net (code "27") (name "Net-(D36-C)") (class "Default")
      (node (ref "C18") (pin "2") (pinfunction "2_2") (pintype "passive"))
      (node (ref "D36") (pin "3") (pinfunction "C_3") (pintype "passive"))
      (node (ref "R24") (pin "2") (pinfunction "2_2") (pintype "passive"))
      (node (ref "U5") (pin "3") (pinfunction "VINN_3") (pintype "input"))
    )
    (net (code "28") (name "Net-(D41-C)") (class "Default")
      (node (ref "C9") (pin "1") (pinfunction "1_1") (pintype "passive"))
      (node (ref "D41") (pin "3") (pinfunction "C_3") (pintype "passive"))
      (node (ref "R14") (pin "2") (pinfunction "2_2") (pintype "passive"))
      (node (ref "R44") (pin "1") (pinfunction "1_1") (pintype "passive"))
      (node (ref "U3") (pin "2") (pinfunction "VINP_2") (pintype "input"))
    )
    (net (code "29") (name "Net-(D42-C)") (class "Default")
      (node (ref "C9") (pin "2") (pinfunction "2_2") (pintype "passive"))
      (node (ref "D42") (pin "3") (pinfunction "C_3") (pintype "passive"))
      (node (ref "R11") (pin "2") (pinfunction "2_2") (pintype "passive"))
      (node (ref "U3") (pin "3") (pinfunction "VINN_3") (pintype "input"))
    )
    (net (code "30") (name "Net-(D47-C)") (class "Default")
      (node (ref "C2") (pin "1") (pinfunction "1_1") (pintype "passive"))
      (node (ref "D47") (pin "3") (pinfunction "C_3") (pintype "passive"))
      (node (ref "R39") (pin "1") (pinfunction "1_1") (pintype "passive"))
      (node (ref "R4") (pin "2") (pinfunction "2_2") (pintype "passive"))
      (node (ref "U1") (pin "2") (pinfunction "VINP_2") (pintype "input"))
    )
    (net (code "31") (name "Net-(D48-C)") (class "Default")
      (node (ref "C2") (pin "2") (pinfunction "2_2") (pintype "passive"))
      (node (ref "D48") (pin "3") (pinfunction "C_3") (pintype "passive"))
      (node (ref "R2") (pin "2") (pinfunction "2_2") (pintype "passive"))
      (node (ref "U1") (pin "3") (pinfunction "VINN_3") (pintype "input"))
    )
    (net (code "32") (name "Net-(FB1-Pad2)") (class "Default")
      (node (ref "FB1") (pin "2") (pinfunction "2_2") (pintype "passive"))
      (node (ref "R2") (pin "1") (pinfunction "1_1") (pintype "passive"))
    )
    (net (code "33") (name "Net-(FB2-Pad1)") (class "Default")
      (node (ref "FB2") (pin "1") (pinfunction "1_1") (pintype "passive"))
      (node (ref "R1") (pin "2") (pinfunction "2_2") (pintype "passive"))
      (node (ref "TP2") (pin "1") (pinfunction "1_1") (pintype "passive"))
    )
    (net (code "34") (name "Net-(FB2-Pad2)") (class "Default")
      (node (ref "FB2") (pin "2") (pinfunction "2_2") (pintype "passive"))
      (node (ref "R4") (pin "1") (pinfunction "1_1") (pintype "passive"))
    )
    (net (code "35") (name "Net-(FB3-Pad2)") (class "Default")
      (node (ref "FB3") (pin "2") (pinfunction "2_2") (pintype "passive"))
      (node (ref "R11") (pin "1") (pinfunction "1_1") (pintype "passive"))
    )
    (net (code "36") (name "Net-(FB4-Pad1)") (class "Default")
      (node (ref "FB4") (pin "1") (pinfunction "1_1") (pintype "passive"))
      (node (ref "R9") (pin "2") (pinfunction "2_2") (pintype "passive"))
      (node (ref "TP5") (pin "1") (pinfunction "1_1") (pintype "passive"))
    )
    (net (code "37") (name "Net-(FB4-Pad2)") (class "Default")
      (node (ref "FB4") (pin "2") (pinfunction "2_2") (pintype "passive"))
      (node (ref "R14") (pin "1") (pinfunction "1_1") (pintype "passive"))
    )
    (net (code "38") (name "Net-(FB5-Pad2)") (class "Default")
      (node (ref "FB5") (pin "2") (pinfunction "2_2") (pintype "passive"))
      (node (ref "R24") (pin "1") (pinfunction "1_1") (pintype "passive"))
    )
    (net (code "39") (name "Net-(FB6-Pad1)") (class "Default")
      (node (ref "FB6") (pin "1") (pinfunction "1_1") (pintype "passive"))
      (node (ref "R22") (pin "2") (pinfunction "2_2") (pintype "passive"))
      (node (ref "TP8") (pin "1") (pinfunction "1_1") (pintype "passive"))
    )
    (net (code "40") (name "Net-(FB6-Pad2)") (class "Default")
      (node (ref "FB6") (pin "2") (pinfunction "2_2") (pintype "passive"))
      (node (ref "R26") (pin "1") (pinfunction "1_1") (pintype "passive"))
    )
    (net (code "41") (name "Net-(U1-VOUTN)") (class "Default")
      (node (ref "R3") (pin "1") (pinfunction "1_1") (pintype "passive"))
      (node (ref "U1") (pin "6") (pinfunction "VOUTN_6") (pintype "output"))
    )
    (net (code "42") (name "Net-(U1-VOUTP)") (class "Default")
      (node (ref "R5") (pin "1") (pinfunction "1_1") (pintype "passive"))
      (node (ref "U1") (pin "7") (pinfunction "VOUTP_7") (pintype "output"))
    )
    (net (code "43") (name "Net-(U3-VOUTN)") (class "Default")
      (node (ref "R12") (pin "1") (pinfunction "1_1") (pintype "passive"))
      (node (ref "U3") (pin "6") (pinfunction "VOUTN_6") (pintype "output"))
    )
    (net (code "44") (name "Net-(U3-VOUTP)") (class "Default")
      (node (ref "R15") (pin "1") (pinfunction "1_1") (pintype "passive"))
      (node (ref "U3") (pin "7") (pinfunction "VOUTP_7") (pintype "output"))
    )
    (net (code "45") (name "Net-(U5-VOUTN)") (class "Default")
      (node (ref "R23") (pin "1") (pinfunction "1_1") (pintype "passive"))
      (node (ref "U5") (pin "6") (pinfunction "VOUTN_6") (pintype "output"))
    )
    (net (code "46") (name "Net-(U5-VOUTP)") (class "Default")
      (node (ref "R25") (pin "1") (pinfunction "1_1") (pintype "passive"))
      (node (ref "U5") (pin "7") (pinfunction "VOUTP_7") (pintype "output"))
    )
  )
)
